# xv11_controller.net
KiCad netlist of a schematic drawn in EAGLE
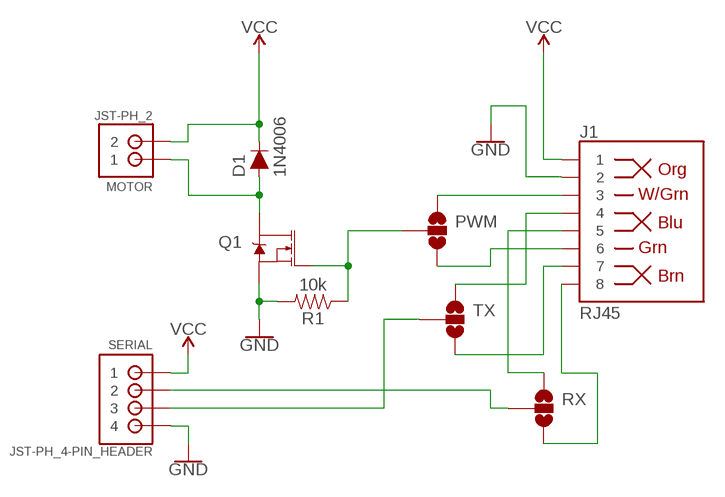
[diagram p0: schematic, sheet 1]

(export (version "E")
  (design (tool "Eeschema 10.0.6"))
  (components
    (comp (ref "D1")
      (value "1N4006")
      (footprint "eagle-import:DIODE-1N4001")
      (libsource (lib "eagle-import") (part "DIODE-PTH"))
    )
    (comp (ref "J1")
      (value "RJ45")
      (footprint "eagle-import:RJ45-8")
      (libsource (lib "eagle-import") (part "RJ45-8"))
    )
    (comp (ref "MOTOR")
      (value "JST-PH_2")
      (footprint "eagle-import:JST_B2B-PH_HEADER")
      (libsource (lib "eagle-import") (part "JST-PH_2-PIN_HEADER"))
    )
    (comp (ref "PWM")
      (value "JUMPER-SMT_3_NO_NO-SILK")
      (footprint "eagle-import:SMT-JUMPER_3_NO_NO-SILK")
      (libsource (lib "eagle-import") (part "JUMPER-SMT_3_NO_NO-SILK"))
    )
    (comp (ref "Q1")
      (value "MOSFET-NCH-FQP30N06L")
      (footprint "eagle-import:TO220V")
      (libsource (lib "eagle-import") (part "MOSFET-NCH-FQP30N06L"))
    )
    (comp (ref "R1")
      (value "10k")
      (footprint "eagle-import:AXIAL-0.3")
      (libsource (lib "eagle-import") (part "1KOHM-HORIZ-1/4W-1%"))
    )
    (comp (ref "RX")
      (value "JUMPER-SMT_3_NO_NO-SILK")
      (footprint "eagle-import:SMT-JUMPER_3_NO_NO-SILK")
      (libsource (lib "eagle-import") (part "JUMPER-SMT_3_NO_NO-SILK"))
    )
    (comp (ref "SERIAL")
      (value "JST-PH_4-PIN_HEADER")
      (footprint "eagle-import:JST_B4B-PH_HEADER")
      (libsource (lib "eagle-import") (part "JST-PH_4-PIN_HEADER"))
    )
    (comp (ref "TX")
      (value "JUMPER-SMT_3_NO_NO-SILK")
      (footprint "eagle-import:SMT-JUMPER_3_NO_NO-SILK")
      (libsource (lib "eagle-import") (part "JUMPER-SMT_3_NO_NO-SILK"))
    )
  )
  (nets
    (net (code "1") (name "GND") (class "Default")
      (node (ref "J1") (pin "2") (pinfunction "2_2") (pintype "bidirectional"))
      (node (ref "Q1") (pin "3") (pinfunction "S_3") (pintype "bidirectional"))
      (node (ref "R1") (pin "P$2") (pinfunction "2_P$2") (pintype "passive"))
      (node (ref "SERIAL") (pin "P4") (pinfunction "4_P4") (pintype "bidirectional"))
    )
    (net (code "2") (name "Net-(J1-Pad3)") (class "Default")
      (node (ref "J1") (pin "3") (pinfunction "3_3") (pintype "bidirectional"))
      (node (ref "PWM") (pin "1") (pinfunction "1_1") (pintype "passive"))
    )
    (net (code "3") (name "Net-(J1-Pad4)") (class "Default")
      (node (ref "J1") (pin "4") (pinfunction "4_4") (pintype "bidirectional"))
      (node (ref "TX") (pin "1") (pinfunction "1_1") (pintype "passive"))
    )
    (net (code "4") (name "Net-(J1-Pad5)") (class "Default")
      (node (ref "J1") (pin "5") (pinfunction "5_5") (pintype "bidirectional"))
      (node (ref "RX") (pin "1") (pinfunction "1_1") (pintype "passive"))
    )
    (net (code "5") (name "Net-(J1-Pad6)") (class "Default")
      (node (ref "J1") (pin "6") (pinfunction "6_6") (pintype "bidirectional"))
      (node (ref "PWM") (pin "3") (pinfunction "3_3") (pintype "passive"))
    )
    (net (code "6") (name "Net-(J1-Pad7)") (class "Default")
      (node (ref "J1") (pin "7") (pinfunction "7_7") (pintype "bidirectional"))
      (node (ref "TX") (pin "3") (pinfunction "3_3") (pintype "passive"))
    )
    (net (code "7") (name "Net-(J1-Pad8)") (class "Default")
      (node (ref "J1") (pin "8") (pinfunction "8_8") (pintype "bidirectional"))
      (node (ref "RX") (pin "3") (pinfunction "3_3") (pintype "passive"))
    )
    (net (code "8") (name "Net-(MOTOR-1)") (class "Default")
      (node (ref "D1") (pin "A") (pinfunction "A_A") (pintype "passive"))
      (node (ref "MOTOR") (pin "P1") (pinfunction "1_P1") (pintype "bidirectional"))
      (node (ref "Q1") (pin "2") (pinfunction "D_2") (pintype "bidirectional"))
    )
    (net (code "9") (name "Net-(Q1-G)") (class "Default")
      (node (ref "PWM") (pin "2") (pinfunction "2_2") (pintype "passive"))
      (node (ref "Q1") (pin "1") (pinfunction "G_1") (pintype "bidirectional"))
      (node (ref "R1") (pin "P$1") (pinfunction "1_P$1") (pintype "passive"))
    )
    (net (code "10") (name "Net-(SERIAL-2)") (class "Default")
      (node (ref "RX") (pin "2") (pinfunction "2_2") (pintype "passive"))
      (node (ref "SERIAL") (pin "P2") (pinfunction "2_P2") (pintype "bidirectional"))
    )
    (net (code "11") (name "Net-(SERIAL-3)") (class "Default")
      (node (ref "SERIAL") (pin "P3") (pinfunction "3_P3") (pintype "bidirectional"))
      (node (ref "TX") (pin "2") (pinfunction "2_2") (pintype "passive"))
    )
    (net (code "12") (name "VCC") (class "Default")
      (node (ref "D1") (pin "C") (pinfunction "C_C") (pintype "passive"))
      (node (ref "J1") (pin "1") (pinfunction "1_1") (pintype "bidirectional"))
      (node (ref "MOTOR") (pin "P2") (pinfunction "2_P2") (pintype "bidirectional"))
      (node (ref "SERIAL") (pin "P1") (pinfunction "1_P1") (pintype "bidirectional"))
    )
  )
)
